# DB-LED_V1_0.net
KiCad netlist of a schematic drawn in Altium Designer
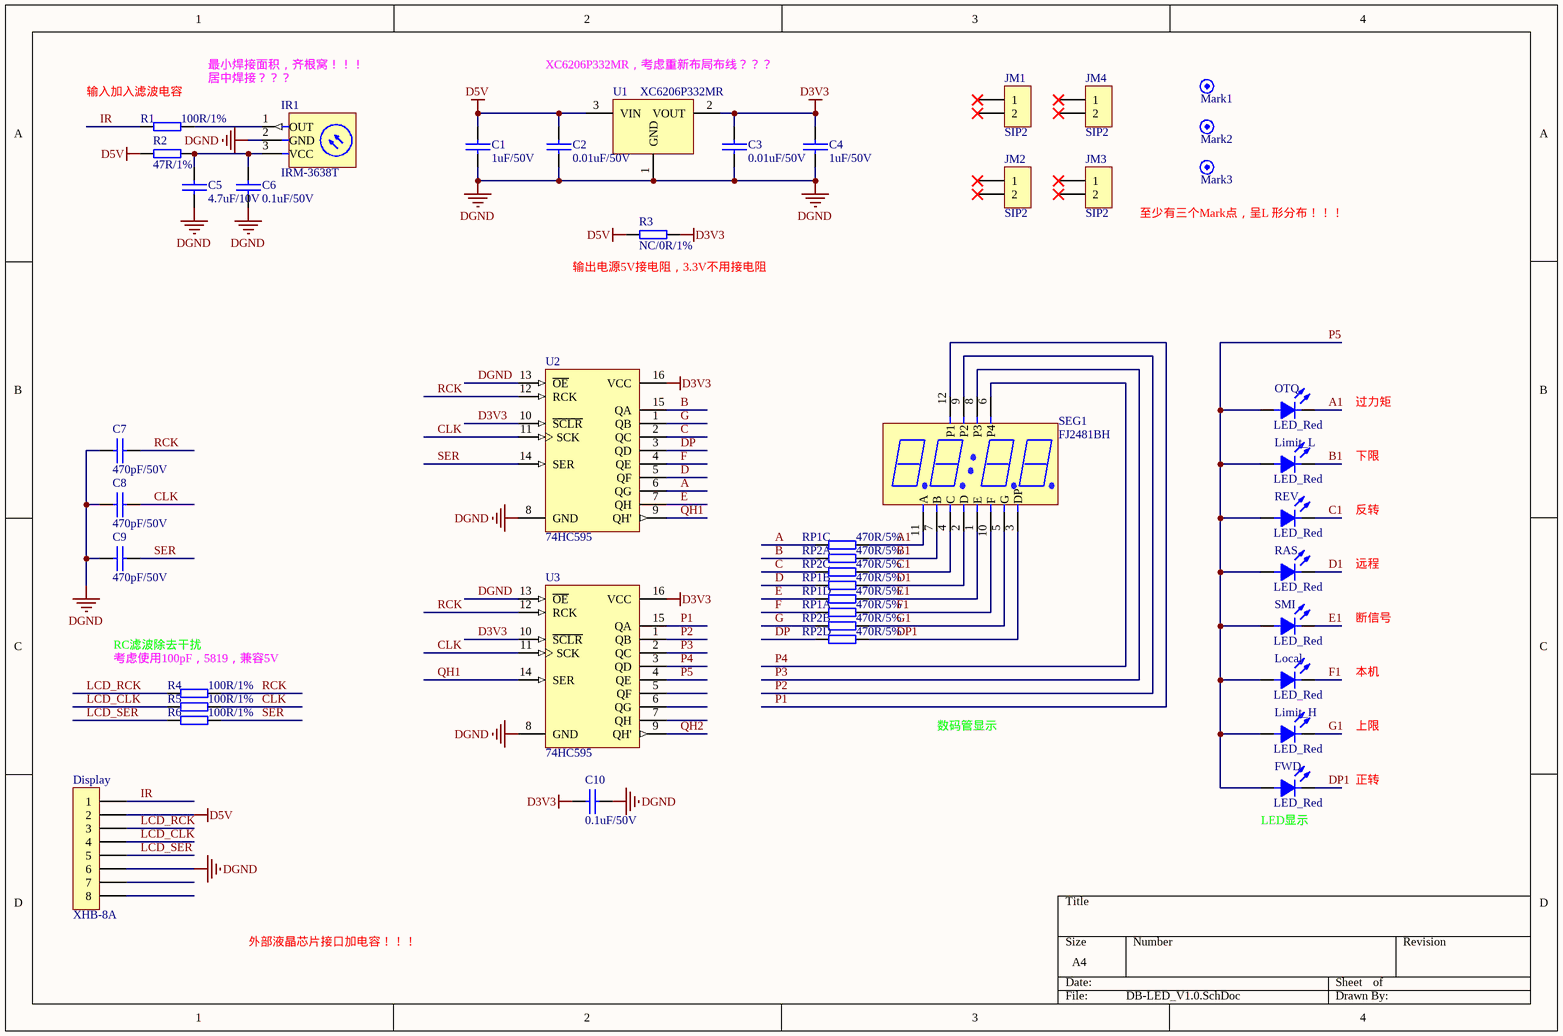
[diagram p0: DB-LED_V1.0.SchDoc]

(export (version "E")
  (design (tool "Eeschema 10.0.6"))
  (components
    (comp (ref "C1")
      (value "1uF/50V")
      (footprint "0603(C)")
      (description "/(X5R)/10%")
      (libsource (lib "ALL_SchLib") (part "Cap"))
    )
    (comp (ref "C2")
      (value "0.01uF/50V")
      (footprint "0603(C)")
      (description "/(X7R)/10%")
      (libsource (lib "ALL_SchLib") (part "Cap"))
    )
    (comp (ref "C3")
      (value "0.01uF/50V")
      (footprint "0603(C)")
      (description "/(X7R)/10%")
      (libsource (lib "ALL_SchLib") (part "Cap"))
    )
    (comp (ref "C4")
      (value "1uF/50V")
      (footprint "0603(C)")
      (description "/(X5R)/10%")
      (libsource (lib "ALL_SchLib") (part "Cap"))
    )
    (comp (ref "C5")
      (value "4.7uF/10V")
      (footprint "0603(C)")
      (description "/(X5R)/10%")
      (libsource (lib "ALL_SchLib") (part "Cap"))
    )
    (comp (ref "C6")
      (value "0.1uF/50V")
      (footprint "0603(C)")
      (description "/(X7R)/10%")
      (libsource (lib "ALL_SchLib") (part "Cap"))
    )
    (comp (ref "C7")
      (value "470pF/50V")
      (footprint "0603(C)")
      (description "/(X7R)/10%")
      (libsource (lib "ALL_SchLib") (part "Cap"))
    )
    (comp (ref "C8")
      (value "470pF/50V")
      (footprint "0603(C)")
      (description "/(X7R)/10%")
      (libsource (lib "ALL_SchLib") (part "Cap"))
    )
    (comp (ref "C9")
      (value "470pF/50V")
      (footprint "0603(C)")
      (description "/(X7R)/10%")
      (libsource (lib "ALL_SchLib") (part "Cap"))
    )
    (comp (ref "C10")
      (value "0.1uF/50V")
      (footprint "0603(C)")
      (description "/(X7R)/10%")
      (libsource (lib "ALL_SchLib") (part "Cap"))
    )
    (comp (ref "Display")
      (value "XHB-8A")
      (footprint "XHB2.5-8A")
      (libsource (lib "ALL_SchLib") (part "CON8"))
    )
    (comp (ref "FWD")
      (value "LED_Red")
      (footprint "LED2-TM[.1]/3")
      (libsource (lib "ALL_SchLib") (part "LED"))
    )
    (comp (ref "IR1")
      (value "IRM-3638T")
      (footprint "IR3-RM6/7")
      (libsource (lib "ALL_SchLib") (part "HS38B"))
    )
    (comp (ref "JM1") (value "SIP2") (footprint "SIP2-TM[.1]") (libsource (lib "ALL_SchLib") (part "CON2")))
    (comp (ref "JM2") (value "SIP2") (footprint "SIP2-TM[.1]") (libsource (lib "ALL_SchLib") (part "CON2")))
    (comp (ref "JM3") (value "SIP2") (footprint "SIP2-TM[.1]") (libsource (lib "ALL_SchLib") (part "CON2")))
    (comp (ref "JM4") (value "SIP2") (footprint "SIP2-TM[.1]") (libsource (lib "ALL_SchLib") (part "CON2")))
    (comp (ref "Limit_H")
      (value "LED_Red")
      (footprint "LED2-TM[.1]/3")
      (libsource (lib "ALL_SchLib") (part "LED"))
    )
    (comp (ref "Limit_L")
      (value "LED_Red")
      (footprint "LED2-TM[.1]/3")
      (libsource (lib "ALL_SchLib") (part "LED"))
    )
    (comp (ref "Local")
      (value "LED_Red")
      (footprint "LED2-TM[.1]/3")
      (libsource (lib "ALL_SchLib") (part "LED"))
    )
    (comp (ref "Mark1")
      (value "Mark")
      (footprint "MARK-3MM[SINGlE]")
      (libsource (lib "New_SchLib") (part "Mark"))
    )
    (comp (ref "Mark2")
      (value "Mark")
      (footprint "MARK-3MM[SINGlE]")
      (libsource (lib "New_SchLib") (part "Mark"))
    )
    (comp (ref "Mark3")
      (value "Mark")
      (footprint "MARK-3MM[SINGlE]")
      (libsource (lib "New_SchLib") (part "Mark"))
    )
    (comp (ref "OTQ")
      (value "LED_Red")
      (footprint "LED2-TM[.1]/3")
      (libsource (lib "ALL_SchLib") (part "LED"))
    )
    (comp (ref "R1") (value "100R/1%") (footprint "0603(R)") (libsource (lib "ALL_SchLib") (part "Res")))
    (comp (ref "R2") (value "47R/1%") (footprint "0603(R)") (libsource (lib "ALL_SchLib") (part "Res")))
    (comp (ref "R3") (value "NC/0R/1%") (footprint "0603(R)") (libsource (lib "ALL_SchLib") (part "Res")))
    (comp (ref "R4") (value "100R/1%") (footprint "0603(R)") (libsource (lib "ALL_SchLib") (part "Res")))
    (comp (ref "R5") (value "100R/1%") (footprint "0603(R)") (libsource (lib "ALL_SchLib") (part "Res")))
    (comp (ref "R6") (value "100R/1%") (footprint "0603(R)") (libsource (lib "ALL_SchLib") (part "Res")))
    (comp (ref "RAS")
      (value "LED_Red")
      (footprint "LED2-TM[.1]/3")
      (libsource (lib "ALL_SchLib") (part "LED"))
    )
    (comp (ref "REV")
      (value "LED_Red")
      (footprint "LED2-TM[.1]/3")
      (libsource (lib "ALL_SchLib") (part "LED"))
    )
    (comp (ref "RP1")
      (value "470R/5%")
      (footprint "4D03(S)")
      (libsource (lib "ALL_SchLib") (part "Res-8P4R"))
    )
    (comp (ref "RP2")
      (value "470R/5%")
      (footprint "4D03(S)")
      (libsource (lib "ALL_SchLib") (part "Res-8P4R"))
    )
    (comp (ref "SEG1")
      (value "FJ2481BH")
      (footprint "SEG4-TM[.3]/[.5]")
      (libsource (lib "ALL_SchLib") (part "LG2841DH"))
    )
    (comp (ref "SMI")
      (value "LED_Red")
      (footprint "LED2-TM[.1]/3")
      (libsource (lib "ALL_SchLib") (part "LED"))
    )
    (comp (ref "U1")
      (value "XC6206P332MR")
      (footprint "SOT23-3-W")
      (libsource (lib "New_SchLib") (part "XC6206PXXXMR"))
    )
    (comp (ref "U2")
      (value "74HC595")
      (footprint "SO16-[.15](S)")
      (libsource (lib "ALL_SchLib") (part "74HC595"))
    )
    (comp (ref "U3")
      (value "74HC595")
      (footprint "SO16-[.15](S)")
      (libsource (lib "ALL_SchLib") (part "74HC595"))
    )
  )
  (nets
    (net (code "1") (name "/A") (class "Default")
      (node (ref "RP1") (pin "6") (pinfunction "6_6") (pintype "passive"))
      (node (ref "U2") (pin "6") (pinfunction "QG_6") (pintype "tri_state"))
    )
    (net (code "2") (name "/A1") (class "Default")
      (node (ref "OTQ") (pin "2") (pinfunction "K_2") (pintype "passive"))
      (node (ref "RP1") (pin "3") (pinfunction "3_3") (pintype "passive"))
      (node (ref "SEG1") (pin "11") (pinfunction "A_11") (pintype "passive"))
    )
    (net (code "3") (name "/B") (class "Default")
      (node (ref "RP2") (pin "8") (pinfunction "8_8") (pintype "passive"))
      (node (ref "U2") (pin "15") (pinfunction "QA_15") (pintype "tri_state"))
    )
    (net (code "4") (name "/B1") (class "Default")
      (node (ref "Limit_L") (pin "2") (pinfunction "K_2") (pintype "passive"))
      (node (ref "RP2") (pin "1") (pinfunction "1_1") (pintype "passive"))
      (node (ref "SEG1") (pin "7") (pinfunction "B_7") (pintype "passive"))
    )
    (net (code "5") (name "/C") (class "Default")
      (node (ref "RP2") (pin "6") (pinfunction "6_6") (pintype "passive"))
      (node (ref "U2") (pin "2") (pinfunction "QC_2") (pintype "tri_state"))
    )
    (net (code "6") (name "/C1") (class "Default")
      (node (ref "REV") (pin "2") (pinfunction "K_2") (pintype "passive"))
      (node (ref "RP2") (pin "3") (pinfunction "3_3") (pintype "passive"))
      (node (ref "SEG1") (pin "4") (pinfunction "C_4") (pintype "passive"))
    )
    (net (code "7") (name "/CLK") (class "Default")
      (node (ref "C8") (pin "1") (pinfunction "1_1") (pintype "passive"))
      (node (ref "R5") (pin "1") (pinfunction "1_1") (pintype "passive"))
      (node (ref "U2") (pin "11") (pinfunction "SCK_11") (pintype "input"))
      (node (ref "U3") (pin "11") (pinfunction "SCK_11") (pintype "input"))
    )
    (net (code "8") (name "/D") (class "Default")
      (node (ref "RP1") (pin "7") (pinfunction "7_7") (pintype "passive"))
      (node (ref "U2") (pin "5") (pinfunction "QF_5") (pintype "tri_state"))
    )
    (net (code "9") (name "/D1") (class "Default")
      (node (ref "RAS") (pin "2") (pinfunction "K_2") (pintype "passive"))
      (node (ref "RP1") (pin "2") (pinfunction "2_2") (pintype "passive"))
      (node (ref "SEG1") (pin "2") (pinfunction "D_2") (pintype "passive"))
    )
    (net (code "10") (name "/DP") (class "Default")
      (node (ref "RP2") (pin "5") (pinfunction "5_5") (pintype "passive"))
      (node (ref "U2") (pin "3") (pinfunction "QD_3") (pintype "tri_state"))
    )
    (net (code "11") (name "/DP1") (class "Default")
      (node (ref "FWD") (pin "2") (pinfunction "K_2") (pintype "passive"))
      (node (ref "RP2") (pin "4") (pinfunction "4_4") (pintype "passive"))
      (node (ref "SEG1") (pin "3") (pinfunction "DP_3") (pintype "passive"))
    )
    (net (code "12") (name "/E") (class "Default")
      (node (ref "RP1") (pin "5") (pinfunction "5_5") (pintype "passive"))
      (node (ref "U2") (pin "7") (pinfunction "QH_7") (pintype "tri_state"))
    )
    (net (code "13") (name "/E1") (class "Default")
      (node (ref "RP1") (pin "4") (pinfunction "4_4") (pintype "passive"))
      (node (ref "SEG1") (pin "1") (pinfunction "E_1") (pintype "passive"))
      (node (ref "SMI") (pin "2") (pinfunction "K_2") (pintype "passive"))
    )
    (net (code "14") (name "/F") (class "Default")
      (node (ref "RP1") (pin "8") (pinfunction "8_8") (pintype "passive"))
      (node (ref "U2") (pin "4") (pinfunction "QE_4") (pintype "tri_state"))
    )
    (net (code "15") (name "/F1") (class "Default")
      (node (ref "Local") (pin "2") (pinfunction "K_2") (pintype "passive"))
      (node (ref "RP1") (pin "1") (pinfunction "1_1") (pintype "passive"))
      (node (ref "SEG1") (pin "10") (pinfunction "F_10") (pintype "passive"))
    )
    (net (code "16") (name "/G") (class "Default")
      (node (ref "RP2") (pin "7") (pinfunction "7_7") (pintype "passive"))
      (node (ref "U2") (pin "1") (pinfunction "QB_1") (pintype "tri_state"))
    )
    (net (code "17") (name "/G1") (class "Default")
      (node (ref "Limit_H") (pin "2") (pinfunction "K_2") (pintype "passive"))
      (node (ref "RP2") (pin "2") (pinfunction "2_2") (pintype "passive"))
      (node (ref "SEG1") (pin "5") (pinfunction "G_5") (pintype "passive"))
    )
    (net (code "18") (name "/IR") (class "Default")
      (node (ref "Display") (pin "1") (pinfunction "1_1") (pintype "passive"))
      (node (ref "R1") (pin "1") (pinfunction "1_1") (pintype "passive"))
    )
    (net (code "19") (name "/LCD_CLK") (class "Default")
      (node (ref "Display") (pin "4") (pinfunction "4_4") (pintype "passive"))
      (node (ref "R5") (pin "2") (pinfunction "2_2") (pintype "passive"))
    )
    (net (code "20") (name "/LCD_RCK") (class "Default")
      (node (ref "Display") (pin "3") (pinfunction "3_3") (pintype "passive"))
      (node (ref "R4") (pin "2") (pinfunction "2_2") (pintype "passive"))
    )
    (net (code "21") (name "/LCD_SER") (class "Default")
      (node (ref "Display") (pin "5") (pinfunction "5_5") (pintype "passive"))
      (node (ref "R6") (pin "2") (pinfunction "2_2") (pintype "passive"))
    )
    (net (code "22") (name "/P1") (class "Default")
      (node (ref "SEG1") (pin "12") (pinfunction "P1_12") (pintype "passive"))
      (node (ref "U3") (pin "15") (pinfunction "QA_15") (pintype "tri_state"))
    )
    (net (code "23") (name "/P2") (class "Default")
      (node (ref "SEG1") (pin "9") (pinfunction "P2_9") (pintype "passive"))
      (node (ref "U3") (pin "1") (pinfunction "QB_1") (pintype "tri_state"))
    )
    (net (code "24") (name "/P3") (class "Default")
      (node (ref "SEG1") (pin "8") (pinfunction "P3_8") (pintype "passive"))
      (node (ref "U3") (pin "2") (pinfunction "QC_2") (pintype "tri_state"))
    )
    (net (code "25") (name "/P4") (class "Default")
      (node (ref "SEG1") (pin "6") (pinfunction "P4_6") (pintype "passive"))
      (node (ref "U3") (pin "3") (pinfunction "QD_3") (pintype "tri_state"))
    )
    (net (code "26") (name "/P5") (class "Default")
      (node (ref "FWD") (pin "1") (pinfunction "A_1") (pintype "passive"))
      (node (ref "Limit_H") (pin "1") (pinfunction "A_1") (pintype "passive"))
      (node (ref "Limit_L") (pin "1") (pinfunction "A_1") (pintype "passive"))
      (node (ref "Local") (pin "1") (pinfunction "A_1") (pintype "passive"))
      (node (ref "OTQ") (pin "1") (pinfunction "A_1") (pintype "passive"))
      (node (ref "RAS") (pin "1") (pinfunction "A_1") (pintype "passive"))
      (node (ref "REV") (pin "1") (pinfunction "A_1") (pintype "passive"))
      (node (ref "SMI") (pin "1") (pinfunction "A_1") (pintype "passive"))
      (node (ref "U3") (pin "4") (pinfunction "QE_4") (pintype "tri_state"))
    )
    (net (code "27") (name "/QH1") (class "Default")
      (node (ref "U2") (pin "9") (pinfunction "QH'_9") (pintype "output"))
      (node (ref "U3") (pin "14") (pinfunction "SER_14") (pintype "input"))
    )
    (net (code "28") (name "/QH2") (class "Default")
      (node (ref "U3") (pin "9") (pinfunction "QH'_9") (pintype "output"))
    )
    (net (code "29") (name "/RCK") (class "Default")
      (node (ref "C7") (pin "1") (pinfunction "1_1") (pintype "passive"))
      (node (ref "R4") (pin "1") (pinfunction "1_1") (pintype "passive"))
      (node (ref "U2") (pin "12") (pinfunction "RCK_12") (pintype "input"))
      (node (ref "U3") (pin "12") (pinfunction "RCK_12") (pintype "input"))
    )
    (net (code "30") (name "/SER") (class "Default")
      (node (ref "C9") (pin "1") (pinfunction "1_1") (pintype "passive"))
      (node (ref "R6") (pin "1") (pinfunction "1_1") (pintype "passive"))
      (node (ref "U2") (pin "14") (pinfunction "SER_14") (pintype "input"))
    )
    (net (code "31") (name "D3V3") (class "Default")
      (node (ref "C10") (pin "1") (pinfunction "1_1") (pintype "passive"))
      (node (ref "C3") (pin "1") (pinfunction "1_1") (pintype "passive"))
      (node (ref "C4") (pin "1") (pinfunction "1_1") (pintype "passive"))
      (node (ref "R3") (pin "1") (pinfunction "1_1") (pintype "passive"))
      (node (ref "U1") (pin "2") (pinfunction "VOUT_2") (pintype "power_in"))
      (node (ref "U2") (pin "10") (pinfunction "~{SCLR}_10") (pintype "input"))
      (node (ref "U2") (pin "16") (pinfunction "VCC_16") (pintype "power_in"))
      (node (ref "U3") (pin "10") (pinfunction "~{SCLR}_10") (pintype "input"))
      (node (ref "U3") (pin "16") (pinfunction "VCC_16") (pintype "power_in"))
    )
    (net (code "32") (name "D5V") (class "Default")
      (node (ref "C1") (pin "1") (pinfunction "1_1") (pintype "passive"))
      (node (ref "C2") (pin "1") (pinfunction "1_1") (pintype "passive"))
      (node (ref "Display") (pin "2") (pinfunction "2_2") (pintype "passive"))
      (node (ref "R2") (pin "1") (pinfunction "1_1") (pintype "passive"))
      (node (ref "R3") (pin "2") (pinfunction "2_2") (pintype "passive"))
      (node (ref "U1") (pin "3") (pinfunction "VIN_3") (pintype "power_in"))
    )
    (net (code "33") (name "DGND") (class "Default")
      (node (ref "C1") (pin "2") (pinfunction "2_2") (pintype "passive"))
      (node (ref "C10") (pin "2") (pinfunction "2_2") (pintype "passive"))
      (node (ref "C2") (pin "2") (pinfunction "2_2") (pintype "passive"))
      (node (ref "C3") (pin "2") (pinfunction "2_2") (pintype "passive"))
      (node (ref "C4") (pin "2") (pinfunction "2_2") (pintype "passive"))
      (node (ref "C5") (pin "2") (pinfunction "2_2") (pintype "passive"))
      (node (ref "C6") (pin "2") (pinfunction "2_2") (pintype "passive"))
      (node (ref "C7") (pin "2") (pinfunction "2_2") (pintype "passive"))
      (node (ref "C8") (pin "2") (pinfunction "2_2") (pintype "passive"))
      (node (ref "C9") (pin "2") (pinfunction "2_2") (pintype "passive"))
      (node (ref "Display") (pin "6") (pinfunction "6_6") (pintype "passive"))
      (node (ref "IR1") (pin "2") (pinfunction "GND_2") (pintype "power_in"))
      (node (ref "U1") (pin "1") (pinfunction "GND_1") (pintype "power_in"))
      (node (ref "U2") (pin "13") (pinfunction "~{OE}_13") (pintype "input"))
      (node (ref "U2") (pin "8") (pinfunction "GND_8") (pintype "power_in"))
      (node (ref "U3") (pin "13") (pinfunction "~{OE}_13") (pintype "input"))
      (node (ref "U3") (pin "8") (pinfunction "GND_8") (pintype "power_in"))
    )
    (net (code "34") (name "Net-(IR1-OUT)") (class "Default")
      (node (ref "IR1") (pin "1") (pinfunction "OUT_1") (pintype "output"))
      (node (ref "R1") (pin "2") (pinfunction "2_2") (pintype "passive"))
    )
    (net (code "35") (name "Net-(IR1-VCC)") (class "Default")
      (node (ref "C5") (pin "1") (pinfunction "1_1") (pintype "passive"))
      (node (ref "C6") (pin "1") (pinfunction "1_1") (pintype "passive"))
      (node (ref "IR1") (pin "3") (pinfunction "VCC_3") (pintype "power_in"))
      (node (ref "R2") (pin "2") (pinfunction "2_2") (pintype "passive"))
    )
    (net (code "36") (name "unconnected-(Display-Pad7)") (class "Default")
      (node (ref "Display") (pin "7") (pinfunction "7_7") (pintype "passive"))
    )
    (net (code "37") (name "unconnected-(Display-Pad8)") (class "Default")
      (node (ref "Display") (pin "8") (pinfunction "8_8") (pintype "passive"))
    )
    (net (code "38") (name "unconnected-(JM1-Pad1)") (class "Default")
      (node (ref "JM1") (pin "1") (pinfunction "1_1") (pintype "passive+no_connect"))
    )
    (net (code "39") (name "unconnected-(JM1-Pad2)") (class "Default")
      (node (ref "JM1") (pin "2") (pinfunction "2_2") (pintype "passive+no_connect"))
    )
    (net (code "40") (name "unconnected-(JM2-Pad1)") (class "Default")
      (node (ref "JM2") (pin "1") (pinfunction "1_1") (pintype "passive+no_connect"))
    )
    (net (code "41") (name "unconnected-(JM2-Pad2)") (class "Default")
      (node (ref "JM2") (pin "2") (pinfunction "2_2") (pintype "passive+no_connect"))
    )
    (net (code "42") (name "unconnected-(JM3-Pad1)") (class "Default")
      (node (ref "JM3") (pin "1") (pinfunction "1_1") (pintype "passive+no_connect"))
    )
    (net (code "43") (name "unconnected-(JM3-Pad2)") (class "Default")
      (node (ref "JM3") (pin "2") (pinfunction "2_2") (pintype "passive+no_connect"))
    )
    (net (code "44") (name "unconnected-(JM4-Pad1)") (class "Default")
      (node (ref "JM4") (pin "1") (pinfunction "1_1") (pintype "passive+no_connect"))
    )
    (net (code "45") (name "unconnected-(JM4-Pad2)") (class "Default")
      (node (ref "JM4") (pin "2") (pinfunction "2_2") (pintype "passive+no_connect"))
    )
    (net (code "46") (name "unconnected-(U3-QF-Pad5)") (class "Default")
      (node (ref "U3") (pin "5") (pinfunction "QF_5") (pintype "tri_state"))
    )
    (net (code "47") (name "unconnected-(U3-QG-Pad6)") (class "Default")
      (node (ref "U3") (pin "6") (pinfunction "QG_6") (pintype "tri_state"))
    )
    (net (code "48") (name "unconnected-(U3-QH-Pad7)") (class "Default")
      (node (ref "U3") (pin "7") (pinfunction "QH_7") (pintype "tri_state"))
    )
  )
)
